# Main.net
KiCad netlist of a schematic drawn in Altium Designer
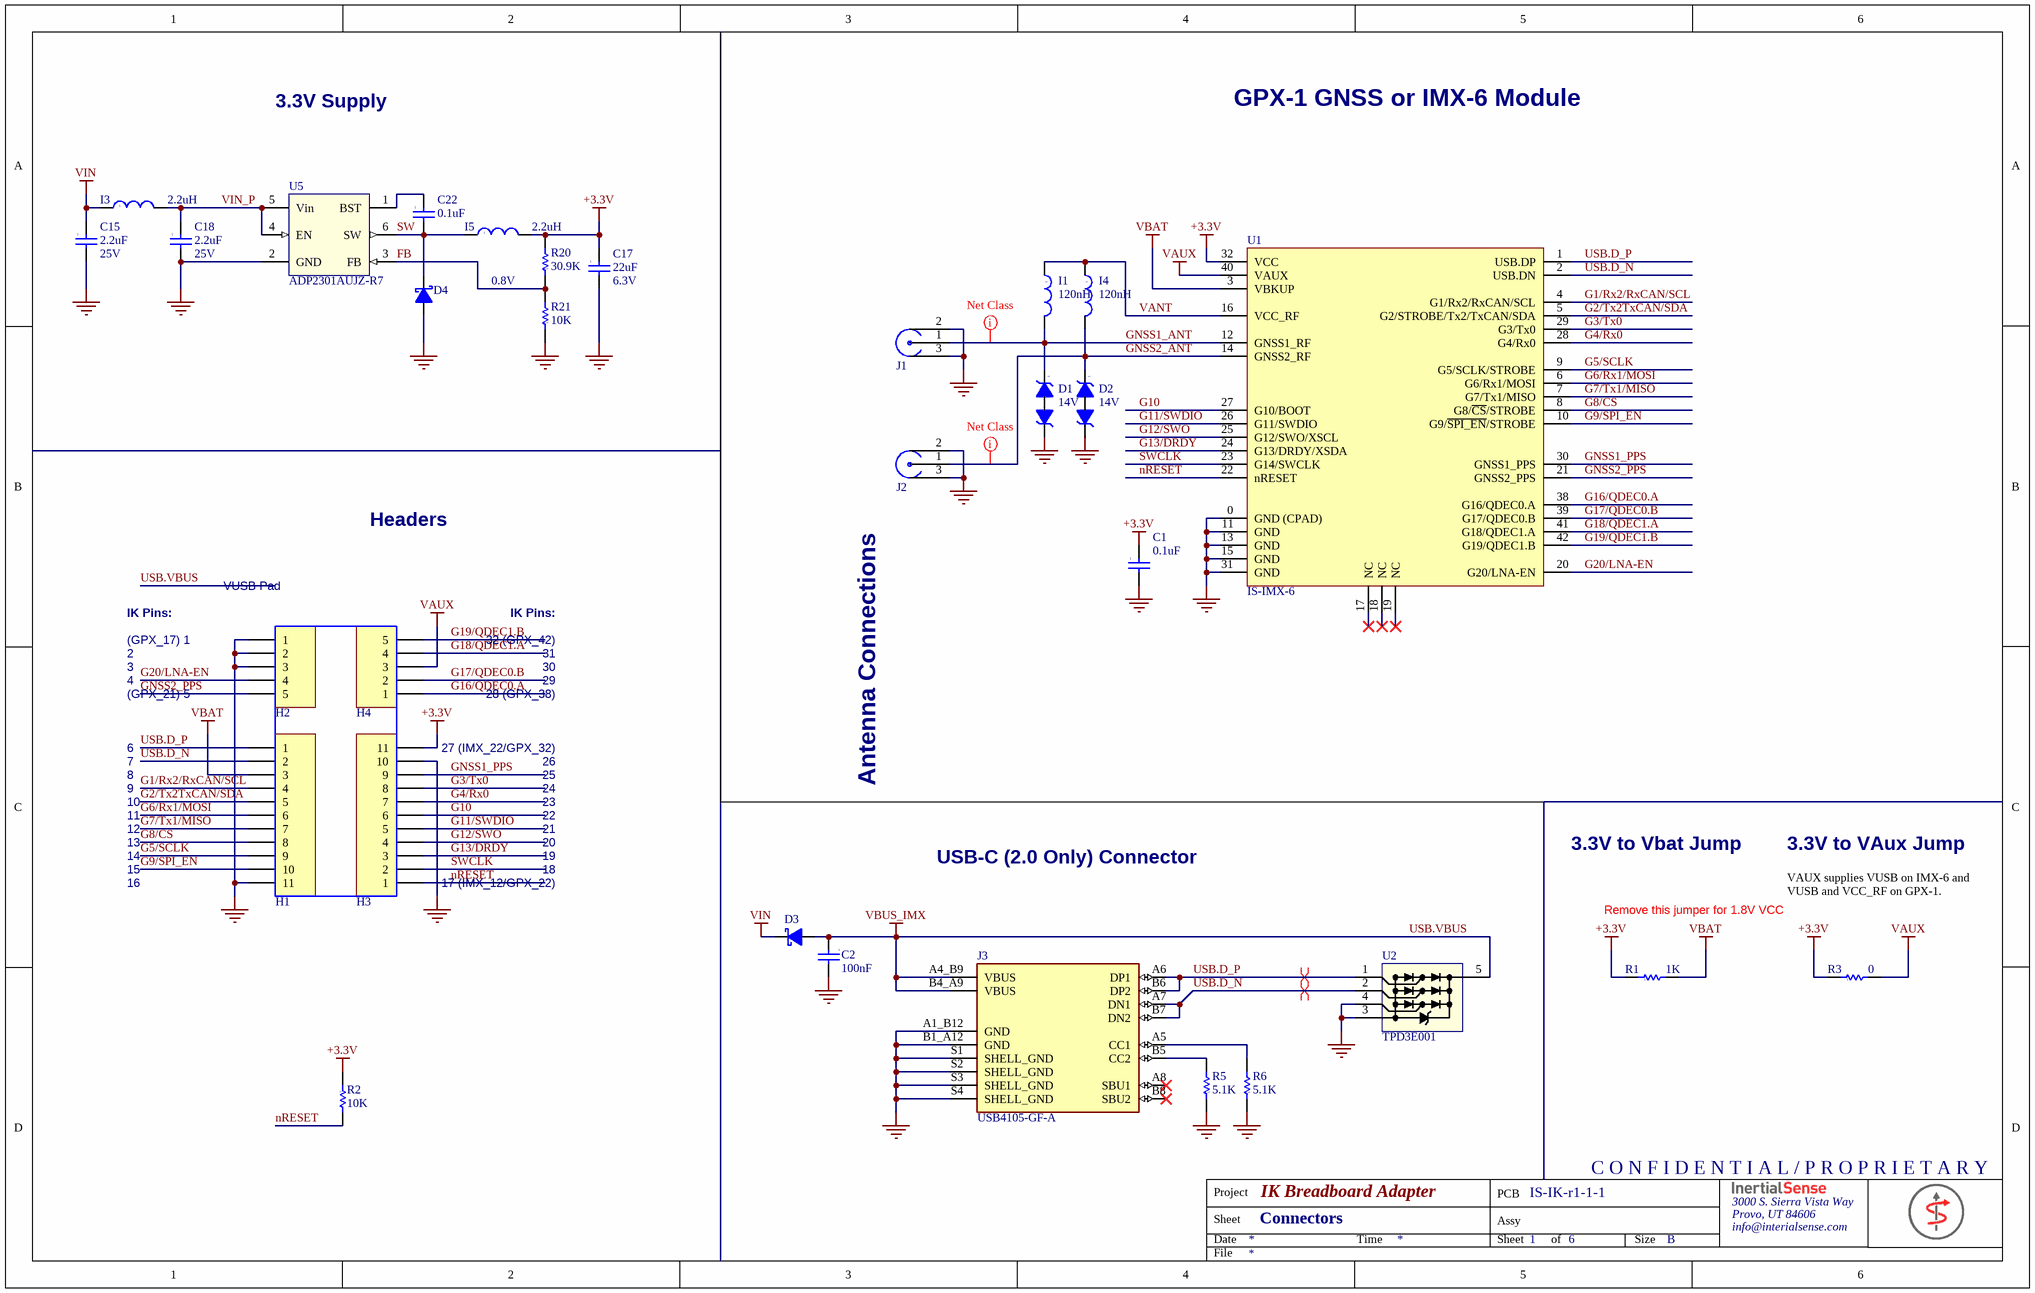
[diagram p0: Main.SchDoc]

(export (version "E")
  (design (tool "Eeschema 10.0.6"))
  (components
    (comp (ref "C1")
      (value "0.1uF")
      (footprint "0402")
      (description "CAP CER .10UF 50V X7R 10% 0402")
      (fields
        (field (name "MANUFACTURER") "TDK Corporation")
        (field (name "MANUFACTURER PART NUMBER") "C1005X7R1H104K")
        (field (name "PUBLISHER") "Altium Limited")
      )
      (libsource (lib "General") (part "Cap"))
    )
    (comp (ref "C2")
      (value "100nF")
      (footprint "0402")
      (description "CAP CER .10UF 50V X7R 10% 0402")
      (fields
        (field (name "MANUFACTURER") "TDK Corporation")
        (field (name "MANUFACTURER PART NUMBER") "C1005X7R1H104K")
        (field (name "PUBLISHER") "Altium Limited")
      )
      (libsource (lib "General") (part "Cap"))
    )
    (comp (ref "C15")
      (value "2.2uF")
      (footprint "0603")
      (description "CAP CER 2.2UF 25V X6S 0603")
      (fields
        (field (name "MANUFACTURER") "Murata")
        (field (name "MANUFACTURER PART NUMBER") "GRT188C81E225KE13D")
        (field (name "VOLTAGE RATING") "25V")
        (field (name "PUBLISHER") "Altium Limited")
      )
      (libsource (lib "General") (part "Cap"))
    )
    (comp (ref "C17")
      (value "22uF")
      (footprint "0603")
      (description "CAP CER 22UF 6.3V X6S 0603")
      (fields
        (field (name "MANUFACTURER") "Murata")
        (field (name "MANUFACTURER PART NUMBER") "GRM188C80J226ME15D")
        (field (name "VOLTAGE RATING") "6.3V")
        (field (name "PUBLISHER") "Altium Limited")
      )
      (libsource (lib "General") (part "Cap"))
    )
    (comp (ref "C18")
      (value "2.2uF")
      (footprint "0603")
      (description "CAP CER 2.2UF 25V X6S 0603")
      (fields
        (field (name "MANUFACTURER") "Murata")
        (field (name "MANUFACTURER PART NUMBER") "GRT188C81E225KE13D")
        (field (name "VOLTAGE RATING") "25V")
        (field (name "PUBLISHER") "Altium Limited")
      )
      (libsource (lib "General") (part "Cap"))
    )
    (comp (ref "C22")
      (value "0.1uF")
      (footprint "0402")
      (description "CAP CER 0.1UF 50V X7R 0402")
      (fields
        (field (name "MANUFACTURER") "TDK")
        (field (name "MANUFACTURER PART NUMBER") "CGA2B3X7R1H104K050BB")
        (field (name "PUBLISHER") "Altium Limited")
      )
      (libsource (lib "General") (part "Cap"))
    )
    (comp (ref "D1")
      (value "Diode - Bidirectional Zener")
      (footprint "R0402")
      (description "LITTELFUSE - PESD0402-140 - DIODE, ESD PROTECTION, 0402, FULL REEL")
      (fields
        (field (name "MANUFACTURER") "Littelfuse")
        (field (name "MANUFACTURER PART NUMBER") "PESD0402-140")
        (field (name "WORKING VOLTAGE") "14V")
      )
      (libsource (lib "General") (part "Diode - Bidirectional Zener"))
    )
    (comp (ref "D2")
      (value "Diode - Bidirectional Zener")
      (footprint "R0402")
      (description "LITTELFUSE - PESD0402-140 - DIODE, ESD PROTECTION, 0402, FULL REEL")
      (fields
        (field (name "MANUFACTURER") "Littelfuse")
        (field (name "MANUFACTURER PART NUMBER") "PESD0402-140")
        (field (name "WORKING VOLTAGE") "14V")
      )
      (libsource (lib "General") (part "Diode - Bidirectional Zener"))
    )
    (comp (ref "D3")
      (value "Diode - Schottky")
      (footprint "D0603B")
      (description "DIODE SCHOTTKY 30V 2A 0603")
      (fields
        (field (name "MANUFACTURER") "Vishay")
        (field (name "MANUFACTURER PART NUMBER") "VSKY20301608-G4-08")
      )
      (libsource (lib "General") (part "Diode - Schottky"))
    )
    (comp (ref "D4")
      (value "Diode - Schottky")
      (footprint "D0603B")
      (description "DIODE SCHOTTKY 30V 2A 0603")
      (fields
        (field (name "MANUFACTURER") "Vishay")
        (field (name "MANUFACTURER PART NUMBER") "VSKY20301608-G4-08")
      )
      (libsource (lib "General") (part "Diode - Schottky"))
    )
    (comp (ref "H1")
      (value "Hdr - 11pin")
      (footprint "Header-.1IN-1x11")
      (description "11 pin header")
      (libsource (lib "IS-IG-BB") (part "Hdr - 11pin"))
    )
    (comp (ref "H2")
      (value "Hdr - 5pin")
      (footprint "Header-.1IN-1x5")
      (description "5 pin header")
      (libsource (lib "") (part "Hdr - 5pin_1"))
    )
    (comp (ref "H3")
      (value "Hdr - 11pin")
      (footprint "Header-.1IN-1x11")
      (description "11 pin header")
      (libsource (lib "") (part "Hdr - 11pin_1"))
    )
    (comp (ref "H4")
      (value "Hdr - 5pin")
      (footprint "Header-.1IN-1x5")
      (description "5 pin header")
      (libsource (lib "IS-IG-BB") (part "Hdr - 5pin"))
    )
    (comp (ref "I1")
      (value "120nH")
      (footprint "0402")
      (description "Inductor RF Chip Wirewound 120nH 5% 100MHz 20Q-Factor 110mA 2.66Ohm DCR 0402 Paper T/R")
      (fields
        (field (name "MANUFACTURER") "Murata")
        (field (name "MANUFACTURER PART NUMBER") "LQW15ANR12J00D")
      )
      (libsource (lib "General") (part "Inductor"))
    )
    (comp (ref "I3")
      (value "2.2uH")
      (footprint "0806")
      (description "FIXED IND 2.2UH 1.2A 110 MOHM")
      (fields
        (field (name "MANUFACTURER") "TDK")
        (field (name "MANUFACTURER PART NUMBER") "MLP2016H2R2MT0S1")
      )
      (libsource (lib "General") (part "Inductor"))
    )
    (comp (ref "I4")
      (value "120nH")
      (footprint "0402")
      (description "Inductor RF Chip Wirewound 120nH 5% 100MHz 20Q-Factor 110mA 2.66Ohm DCR 0402 Paper T/R")
      (fields
        (field (name "MANUFACTURER") "Murata")
        (field (name "MANUFACTURER PART NUMBER") "LQW15ANR12J00D")
      )
      (libsource (lib "General") (part "Inductor"))
    )
    (comp (ref "I5")
      (value "2.2uH")
      (footprint "0806")
      (description "FIXED IND 2.2UH 1.2A 110 MOHM")
      (fields
        (field (name "MANUFACTURER") "TDK")
        (field (name "MANUFACTURER PART NUMBER") "MLP2016H2R2MT0S1")
      )
      (libsource (lib "General") (part "Inductor"))
    )
    (comp (ref "J1")
      (value "RF - GND x 2")
      (footprint "RF UMC SMD")
      (description "CONN UMC RCPT STR 50 OHM SMD")
      (fields
        (field (name "MANUFACTURER") "Emerson Network Power Connectivity Johnson")
        (field (name "MANUFACTURER PART NUMBER") "128-0711-201")
      )
      (libsource (lib "Connectors") (part "RF - GND x 2"))
    )
    (comp (ref "J2")
      (value "RF - GND x 2")
      (footprint "RF UMC SMD")
      (description "CONN UMC RCPT STR 50 OHM SMD")
      (fields
        (field (name "MANUFACTURER") "Emerson Network Power Connectivity Johnson")
        (field (name "MANUFACTURER PART NUMBER") "128-0711-201")
      )
      (libsource (lib "Connectors") (part "RF - GND x 2"))
    )
    (comp (ref "J3")
      (value "USB4105-GF-A")
      (footprint "GCT_USB4105-GF-A")
      (fields (field (name "MANUFACTURER") "GCT"))
      (libsource (lib "Connectors") (part "USB4105-GF-A"))
    )
    (comp (ref "R1")
      (value "1K")
      (footprint "R0402")
      (description "1 kOhms 1/16W Chip Resistor 0402 (1005 Metric) Moisture Resistant Thick Film")
      (fields
        (field (name "MANUFACTURER") "Yageo")
        (field (name "MANUFACTURER PART NUMBER") "RC0402FR-071KL")
      )
      (libsource (lib "General") (part "Res"))
    )
    (comp (ref "R2")
      (value "10K")
      (footprint "R0402")
      (description "10 kOhms 1/16W Chip Resistor 0402 (1005 Metric) Moisture Resistant Thick Film")
      (fields
        (field (name "MANUFACTURER") "Stackpole Electronics")
        (field (name "MANUFACTURER PART NUMBER") "RMCF0402FT10K0")
      )
      (libsource (lib "General") (part "Res"))
    )
    (comp (ref "R3")
      (value "0")
      (footprint "R0402")
      (description "0 Ohms 1/16W Chip Resistor 0402 (1005 Metric) Moisture Resistant Thick Film")
      (fields
        (field (name "MANUFACTURER") "Yageo")
        (field (name "MANUFACTURER PART NUMBER") "RC0402JR-070RL")
      )
      (libsource (lib "General") (part "Res"))
    )
    (comp (ref "R5")
      (value "5.1K")
      (footprint "R0402")
      (description "Res Thick Film 1.0 x 0.5 mm 5.1K Ohm 1% 0.063W(1/16W) 100ppm/ C Molded SMD Paper T/R")
      (fields
        (field (name "MANUFACTURER") "Yageo")
        (field (name "MANUFACTURER PART NUMBER") "RC0402FR-075K1L")
      )
      (libsource (lib "General") (part "Res"))
    )
    (comp (ref "R6")
      (value "5.1K")
      (footprint "R0402")
      (description "Res Thick Film 1.0 x 0.5 mm 5.1K Ohm 1% 0.063W(1/16W) 100ppm/ C Molded SMD Paper T/R")
      (fields
        (field (name "MANUFACTURER") "Yageo")
        (field (name "MANUFACTURER PART NUMBER") "RC0402FR-075K1L")
      )
      (libsource (lib "General") (part "Res"))
    )
    (comp (ref "R20")
      (value "30.9K")
      (footprint "R0402")
      (description "RES TF 30.9K OHM 1% 1/16W 0402")
      (fields
        (field (name "MANUFACTURER") "Stackpole Electronics Inc")
        (field (name "MANUFACTURER PART NUMBER") "RMCF0402FT30K9")
      )
      (libsource (lib "General") (part "Res"))
    )
    (comp (ref "R21")
      (value "10K")
      (footprint "R0402")
      (description "RES 10.0K OHM 1/16W 1% 0402 SMD")
      (fields
        (field (name "MANUFACTURER") "Yageo")
        (field (name "MANUFACTURER PART NUMBER") "RC0402FR-0710KL")
      )
      (libsource (lib "General") (part "Res"))
    )
    (comp (ref "U1")
      (value "IMX")
      (footprint "IS-GPX-1.0")
      (description "Inertial Sense IMX")
      (fields
        (field (name "MANUFACTURER") "Inertial Sense")
        (field (name "MANUFACTURER PART NUMBER") "IS-IMX-6")
      )
      (libsource (lib "IS-GPX-1") (part "IS-GPX-1.0"))
    )
    (comp (ref "U2")
      (value "TPD3E001")
      (footprint "SOTFL50P160X60-5N")
      (description "TVS DIODE 5.5V SOT5")
      (fields
        (field (name "MANUFACTURER") "Texas Instruments")
        (field (name "MANUFACTURER PART NUMBER") "TPD3E001DRLR")
      )
      (libsource (lib "ICs") (part "TPD3E001"))
    )
    (comp (ref "U5")
      (value "ADP2301")
      (footprint "MO-178-AB")
      (description "IC BUCK ADJ 1.2A 6TSOT")
      (fields
        (field (name "MANUFACTURER") "Analog Devices Inc")
        (field (name "MANUFACTURER PART NUMBER") "ADP2301AUJZ-R7")
      )
      (libsource (lib "ICs") (part "ADP2301"))
    )
  )
  (nets
    (net (code "1") (name "+3.3V") (class "Default")
      (node (ref "C1") (pin "1") (pinfunction "1_1") (pintype "passive"))
      (node (ref "C17") (pin "1") (pinfunction "1_1") (pintype "passive"))
      (node (ref "H3") (pin "11") (pinfunction "11_11") (pintype "passive"))
      (node (ref "I5") (pin "2") (pinfunction "2_2") (pintype "passive"))
      (node (ref "R1") (pin "1") (pinfunction "1_1") (pintype "passive"))
      (node (ref "R2") (pin "1") (pinfunction "1_1") (pintype "passive"))
      (node (ref "R20") (pin "2") (pinfunction "2_2") (pintype "passive"))
      (node (ref "R3") (pin "1") (pinfunction "1_1") (pintype "passive"))
      (node (ref "U1") (pin "32") (pinfunction "VCC_32") (pintype "power_in"))
    )
    (net (code "2") (name "/FB") (class "Default")
      (node (ref "R20") (pin "1") (pinfunction "1_1") (pintype "passive"))
      (node (ref "R21") (pin "2") (pinfunction "2_2") (pintype "passive"))
      (node (ref "U5") (pin "3") (pinfunction "FB_3") (pintype "input"))
    )
    (net (code "3") (name "/G1{slash}Rx2{slash}RxCAN{slash}SCL") (class "Default")
      (node (ref "H1") (pin "4") (pinfunction "4_4") (pintype "passive"))
      (node (ref "U1") (pin "4") (pinfunction "G1/Rx2/RxCAN/SCL_4") (pintype "passive"))
    )
    (net (code "4") (name "/G2{slash}Tx2TxCAN{slash}SDA") (class "Default")
      (node (ref "H1") (pin "5") (pinfunction "5_5") (pintype "passive"))
      (node (ref "U1") (pin "5") (pinfunction "G2/STROBE/Tx2/TxCAN/SDA_5") (pintype "passive"))
    )
    (net (code "5") (name "/G3{slash}Tx0") (class "Default")
      (node (ref "H3") (pin "8") (pinfunction "8_8") (pintype "passive"))
      (node (ref "U1") (pin "29") (pinfunction "G3/Tx0_29") (pintype "passive"))
    )
    (net (code "6") (name "/G4{slash}Rx0") (class "Default")
      (node (ref "H3") (pin "7") (pinfunction "7_7") (pintype "passive"))
      (node (ref "U1") (pin "28") (pinfunction "G4/Rx0_28") (pintype "passive"))
    )
    (net (code "7") (name "/G5{slash}SCLK") (class "Default")
      (node (ref "H1") (pin "9") (pinfunction "9_9") (pintype "passive"))
      (node (ref "U1") (pin "9") (pinfunction "G5/SCLK/STROBE_9") (pintype "passive"))
    )
    (net (code "8") (name "/G6{slash}Rx1{slash}MOSI") (class "Default")
      (node (ref "H1") (pin "6") (pinfunction "6_6") (pintype "passive"))
      (node (ref "U1") (pin "6") (pinfunction "G6/Rx1/MOSI_6") (pintype "passive"))
    )
    (net (code "9") (name "/G7{slash}Tx1{slash}MISO") (class "Default")
      (node (ref "H1") (pin "7") (pinfunction "7_7") (pintype "passive"))
      (node (ref "U1") (pin "7") (pinfunction "G7/Tx1/MISO_7") (pintype "passive"))
    )
    (net (code "10") (name "/G8{slash}~{CS}") (class "Default")
      (node (ref "H1") (pin "8") (pinfunction "8_8") (pintype "passive"))
      (node (ref "U1") (pin "8") (pinfunction "G8/~{CS}/STROBE_8") (pintype "passive"))
    )
    (net (code "11") (name "/G9{slash}~{SPI_EN}") (class "Default")
      (node (ref "H1") (pin "10") (pinfunction "10_10") (pintype "passive"))
      (node (ref "U1") (pin "10") (pinfunction "G9/~{SPI_EN}/STROBE_10") (pintype "passive"))
    )
    (net (code "12") (name "/G10") (class "Default")
      (node (ref "H3") (pin "6") (pinfunction "6_6") (pintype "passive"))
      (node (ref "U1") (pin "27") (pinfunction "G10/BOOT_27") (pintype "passive"))
    )
    (net (code "13") (name "/G11{slash}SWDIO") (class "Default")
      (node (ref "H3") (pin "5") (pinfunction "5_5") (pintype "passive"))
      (node (ref "U1") (pin "26") (pinfunction "G11/SWDIO_26") (pintype "passive"))
    )
    (net (code "14") (name "/G12{slash}SWO") (class "Default")
      (node (ref "H3") (pin "4") (pinfunction "4_4") (pintype "passive"))
      (node (ref "U1") (pin "25") (pinfunction "G12/SWO/XSCL_25") (pintype "passive"))
    )
    (net (code "15") (name "/G13{slash}DRDY") (class "Default")
      (node (ref "H3") (pin "3") (pinfunction "3_3") (pintype "passive"))
      (node (ref "U1") (pin "24") (pinfunction "G13/DRDY/XSDA_24") (pintype "passive"))
    )
    (net (code "16") (name "/G16{slash}QDEC0.A") (class "Default")
      (node (ref "H4") (pin "1") (pinfunction "1_1") (pintype "passive"))
      (node (ref "U1") (pin "38") (pinfunction "G16/QDEC0.A_38") (pintype "passive"))
    )
    (net (code "17") (name "/G17{slash}QDEC0.B") (class "Default")
      (node (ref "H4") (pin "2") (pinfunction "2_2") (pintype "passive"))
      (node (ref "U1") (pin "39") (pinfunction "G17/QDEC0.B_39") (pintype "passive"))
    )
    (net (code "18") (name "/G18{slash}QDEC1.A") (class "Default")
      (node (ref "H4") (pin "4") (pinfunction "4_4") (pintype "passive"))
      (node (ref "U1") (pin "41") (pinfunction "G18/QDEC1.A_41") (pintype "passive"))
    )
    (net (code "19") (name "/G19{slash}QDEC1.B") (class "Default")
      (node (ref "H4") (pin "5") (pinfunction "5_5") (pintype "passive"))
      (node (ref "U1") (pin "42") (pinfunction "G19/QDEC1.B_42") (pintype "passive"))
    )
    (net (code "20") (name "/G20{slash}LNA-EN") (class "Default")
      (node (ref "H2") (pin "4") (pinfunction "4_4") (pintype "passive"))
      (node (ref "U1") (pin "20") (pinfunction "G20/LNA-EN_20") (pintype "passive"))
    )
    (net (code "21") (name "/GNSS1_ANT") (class "Default")
      (node (ref "D1") (pin "1") (pinfunction "1_1") (pintype "passive"))
      (node (ref "I1") (pin "2") (pinfunction "2_2") (pintype "passive"))
      (node (ref "J1") (pin "1") (pinfunction "1_1") (pintype "passive"))
      (node (ref "U1") (pin "12") (pinfunction "GNSS1_RF_12") (pintype "passive"))
    )
    (net (code "22") (name "/GNSS1_PPS") (class "Default")
      (node (ref "H3") (pin "9") (pinfunction "9_9") (pintype "passive"))
      (node (ref "U1") (pin "30") (pinfunction "GNSS1_PPS_30") (pintype "passive"))
    )
    (net (code "23") (name "/GNSS2_ANT") (class "Default")
      (node (ref "D2") (pin "1") (pinfunction "1_1") (pintype "passive"))
      (node (ref "I4") (pin "2") (pinfunction "2_2") (pintype "passive"))
      (node (ref "J2") (pin "1") (pinfunction "1_1") (pintype "passive"))
      (node (ref "U1") (pin "14") (pinfunction "GNSS2_RF_14") (pintype "passive"))
    )
    (net (code "24") (name "/GNSS2_PPS") (class "Default")
      (node (ref "H2") (pin "5") (pinfunction "5_5") (pintype "passive"))
      (node (ref "U1") (pin "21") (pinfunction "GNSS2_PPS_21") (pintype "passive"))
    )
    (net (code "25") (name "/SW") (class "Default")
      (node (ref "C22") (pin "2") (pinfunction "2_2") (pintype "passive"))
      (node (ref "D4") (pin "C") (pinfunction "C_C") (pintype "passive"))
      (node (ref "I5") (pin "1") (pinfunction "1_1") (pintype "passive"))
      (node (ref "U5") (pin "6") (pinfunction "SW_6") (pintype "output"))
    )
    (net (code "26") (name "/SWCLK") (class "Default")
      (node (ref "H3") (pin "2") (pinfunction "2_2") (pintype "passive"))
      (node (ref "U1") (pin "23") (pinfunction "G14/SWCLK_23") (pintype "passive"))
    )
    (net (code "27") (name "/USB.D_N") (class "Default")
      (node (ref "H1") (pin "2") (pinfunction "2_2") (pintype "passive"))
      (node (ref "J3") (pin "A7") (pinfunction "DN1_A7") (pintype "bidirectional"))
      (node (ref "J3") (pin "B7") (pinfunction "DN2_B7") (pintype "bidirectional"))
      (node (ref "U1") (pin "2") (pinfunction "USB.DN_2") (pintype "passive"))
      (node (ref "U2") (pin "2") (pintype "passive"))
    )
    (net (code "28") (name "/USB.D_P") (class "Default")
      (node (ref "H1") (pin "1") (pinfunction "1_1") (pintype "passive"))
      (node (ref "J3") (pin "A6") (pinfunction "DP1_A6") (pintype "bidirectional"))
      (node (ref "J3") (pin "B6") (pinfunction "DP2_B6") (pintype "bidirectional"))
      (node (ref "U1") (pin "1") (pinfunction "USB.DP_1") (pintype "passive"))
      (node (ref "U2") (pin "1") (pintype "passive"))
    )
    (net (code "29") (name "/VANT") (class "Default")
      (node (ref "I1") (pin "1") (pinfunction "1_1") (pintype "passive"))
      (node (ref "I4") (pin "1") (pinfunction "1_1") (pintype "passive"))
      (node (ref "U1") (pin "16") (pinfunction "VCC_RF_16") (pintype "power_in"))
    )
    (net (code "30") (name "/VIN_P") (class "Default")
      (node (ref "C18") (pin "1") (pinfunction "1_1") (pintype "passive"))
      (node (ref "I3") (pin "2") (pinfunction "2_2") (pintype "passive"))
      (node (ref "U5") (pin "4") (pinfunction "EN_4") (pintype "input"))
      (node (ref "U5") (pin "5") (pinfunction "Vin_5") (pintype "power_in"))
    )
    (net (code "31") (name "/nRESET") (class "Default")
      (node (ref "H3") (pin "1") (pinfunction "1_1") (pintype "passive"))
      (node (ref "R2") (pin "2") (pinfunction "2_2") (pintype "passive"))
      (node (ref "U1") (pin "22") (pinfunction "nRESET_22") (pintype "passive"))
    )
    (net (code "32") (name "GND") (class "Default")
      (node (ref "C1") (pin "2") (pinfunction "2_2") (pintype "passive"))
      (node (ref "C15") (pin "2") (pinfunction "2_2") (pintype "passive"))
      (node (ref "C17") (pin "2") (pinfunction "2_2") (pintype "passive"))
      (node (ref "C18") (pin "2") (pinfunction "2_2") (pintype "passive"))
      (node (ref "C2") (pin "2") (pinfunction "2_2") (pintype "passive"))
      (node (ref "D1") (pin "2") (pinfunction "2_2") (pintype "passive"))
      (node (ref "D2") (pin "2") (pinfunction "2_2") (pintype "passive"))
      (node (ref "D4") (pin "A") (pinfunction "A_A") (pintype "passive"))
      (node (ref "H1") (pin "11") (pinfunction "11_11") (pintype "passive"))
      (node (ref "H2") (pin "1") (pinfunction "1_1") (pintype "passive"))
      (node (ref "H2") (pin "2") (pinfunction "2_2") (pintype "passive"))
      (node (ref "H2") (pin "3") (pinfunction "3_3") (pintype "passive"))
      (node (ref "H3") (pin "10") (pinfunction "10_10") (pintype "passive"))
      (node (ref "J1") (pin "2") (pinfunction "2_2") (pintype "passive"))
      (node (ref "J1") (pin "3") (pinfunction "3_3") (pintype "passive"))
      (node (ref "J2") (pin "2") (pinfunction "2_2") (pintype "passive"))
      (node (ref "J2") (pin "3") (pinfunction "3_3") (pintype "passive"))
      (node (ref "J3") (pin "A1_B12") (pinfunction "GND_A1_B12") (pintype "power_in"))
      (node (ref "J3") (pin "B1_A12") (pinfunction "GND_B1_A12") (pintype "power_in"))
      (node (ref "J3") (pin "S1") (pinfunction "SHELL_GND_S1") (pintype "power_in"))
      (node (ref "J3") (pin "S2") (pinfunction "SHELL_GND_S2") (pintype "power_in"))
      (node (ref "J3") (pin "S3") (pinfunction "SHELL_GND_S3") (pintype "power_in"))
      (node (ref "J3") (pin "S4") (pinfunction "SHELL_GND_S4") (pintype "power_in"))
      (node (ref "R21") (pin "1") (pinfunction "1_1") (pintype "passive"))
      (node (ref "R5") (pin "1") (pinfunction "1_1") (pintype "passive"))
      (node (ref "R6") (pin "1") (pinfunction "1_1") (pintype "passive"))
      (node (ref "U1") (pin "0") (pinfunction "GND_(CPAD)_0") (pintype "power_in"))
      (node (ref "U1") (pin "11") (pinfunction "GND_11") (pintype "power_in"))
      (node (ref "U1") (pin "13") (pinfunction "GND_13") (pintype "power_in"))
      (node (ref "U1") (pin "15") (pinfunction "GND_15") (pintype "power_in"))
      (node (ref "U1") (pin "31") (pinfunction "GND_31") (pintype "power_in"))
      (node (ref "U2") (pin "3") (pintype "passive"))
      (node (ref "U2") (pin "4") (pinfunction "nc_4") (pintype "passive"))
      (node (ref "U5") (pin "2") (pinfunction "GND_2") (pintype "power_in"))
    )
    (net (code "33") (name "Net-(J3-CC1)") (class "Default")
      (node (ref "J3") (pin "A5") (pinfunction "CC1_A5") (pintype "bidirectional"))
      (node (ref "R6") (pin "2") (pinfunction "2_2") (pintype "passive"))
    )
    (net (code "34") (name "Net-(J3-CC2)") (class "Default")
      (node (ref "J3") (pin "B5") (pinfunction "CC2_B5") (pintype "bidirectional"))
      (node (ref "R5") (pin "2") (pinfunction "2_2") (pintype "passive"))
    )
    (net (code "35") (name "Net-(U5-BST)") (class "Default")
      (node (ref "C22") (pin "1") (pinfunction "1_1") (pintype "passive"))
      (node (ref "U5") (pin "1") (pinfunction "BST_1") (pintype "passive"))
    )
    (net (code "36") (name "VAUX") (class "Default")
      (node (ref "H4") (pin "3") (pinfunction "3_3") (pintype "passive"))
      (node (ref "R3") (pin "2") (pinfunction "2_2") (pintype "passive"))
      (node (ref "U1") (pin "40") (pinfunction "VAUX_40") (pintype "power_in"))
    )
    (net (code "37") (name "VBAT") (class "Default")
      (node (ref "H1") (pin "3") (pinfunction "3_3") (pintype "passive"))
      (node (ref "R1") (pin "2") (pinfunction "2_2") (pintype "passive"))
      (node (ref "U1") (pin "3") (pinfunction "VBKUP_3") (pintype "passive"))
    )
    (net (code "38") (name "VBUS_IMX") (class "Default")
      (node (ref "C2") (pin "1") (pinfunction "1_1") (pintype "passive"))
      (node (ref "D3") (pin "A") (pinfunction "A_A") (pintype "passive"))
      (node (ref "J3") (pin "A4_B9") (pinfunction "VBUS_A4_B9") (pintype "passive"))
      (node (ref "J3") (pin "B4_A9") (pinfunction "VBUS_B4_A9") (pintype "passive"))
      (node (ref "U2") (pin "5") (pinfunction "nc_5") (pintype "passive"))
    )
    (net (code "39") (name "VIN") (class "Default")
      (node (ref "C15") (pin "1") (pinfunction "1_1") (pintype "passive"))
      (node (ref "D3") (pin "C") (pinfunction "C_C") (pintype "passive"))
      (node (ref "I3") (pin "1") (pinfunction "1_1") (pintype "passive"))
    )
    (net (code "40") (name "unconnected-(J3-SBU1-PadA8)") (class "Default")
      (node (ref "J3") (pin "A8") (pinfunction "SBU1_A8") (pintype "bidirectional+no_connect"))
    )
    (net (code "41") (name "unconnected-(J3-SBU2-PadB8)") (class "Default")
      (node (ref "J3") (pin "B8") (pinfunction "SBU2_B8") (pintype "bidirectional+no_connect"))
    )
    (net (code "42") (name "unconnected-(U1-NC-Pad17)") (class "Default")
      (node (ref "U1") (pin "17") (pinfunction "NC_17") (pintype "passive+no_connect"))
    )
    (net (code "43") (name "unconnected-(U1-NC-Pad18)") (class "Default")
      (node (ref "U1") (pin "18") (pinfunction "NC_18") (pintype "passive+no_connect"))
    )
    (net (code "44") (name "unconnected-(U1-NC-Pad19)") (class "Default")
      (node (ref "U1") (pin "19") (pinfunction "NC_19") (pintype "passive+no_connect"))
    )
  )
)
